# CT.net
KiCad netlist of a schematic drawn in EasyEDA Pro
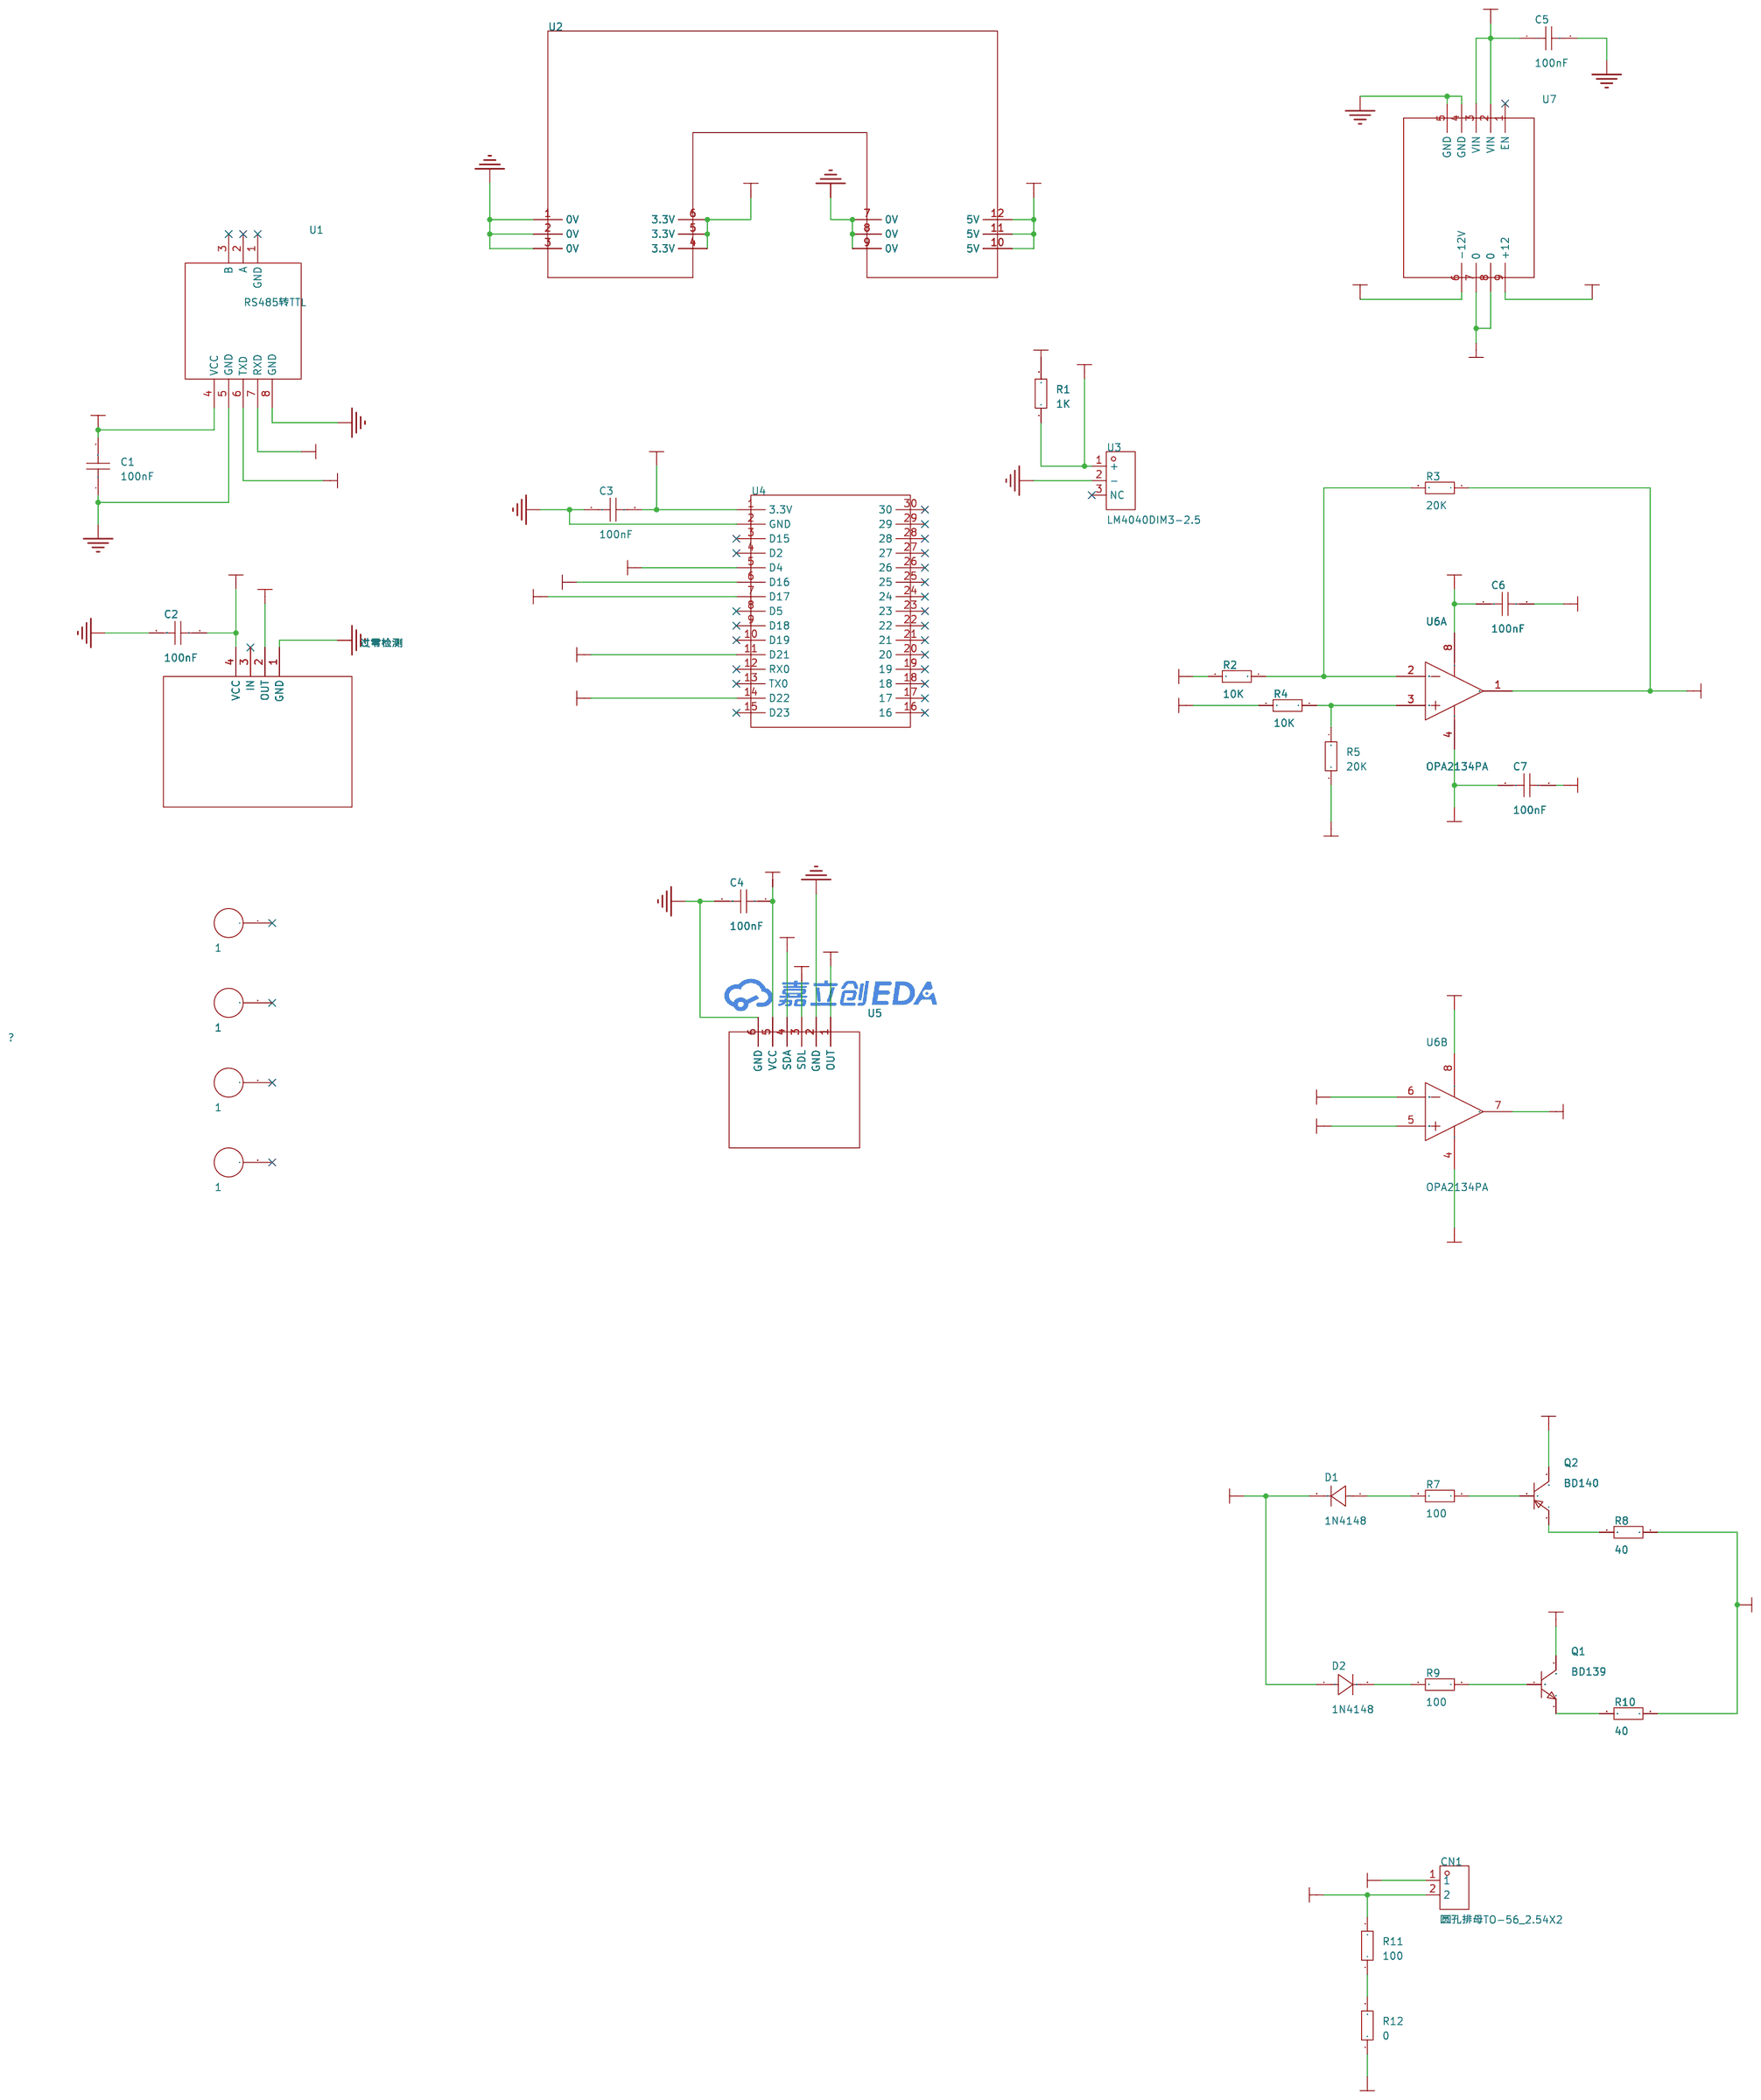
[diagram p0: schematic sheet]

(export (version "E")
  (design (tool "Eeschema 10.0.6"))
  (components
    (comp (ref "C1")
      (value "100nF")
      (footprint "easyedapro:C0805")
      (description "容值:100uF;精度:±20%;额定电压:4V;温度系数:X6S;")
      (fields
        (field (name "Manufacturer Part") "CGA0805X6S107M4R0MT")
        (field (name "Manufacturer") "HRE(芯声)")
      )
      (libsource (lib "easyedapro") (part "CGA0805X6S107M4R0MT"))
    )
    (comp (ref "C2")
      (value "100nF")
      (footprint "easyedapro:C0805")
      (description "容值:100uF;精度:±20%;额定电压:4V;温度系数:X6S;")
      (fields
        (field (name "Manufacturer Part") "CGA0805X6S107M4R0MT")
        (field (name "Manufacturer") "HRE(芯声)")
      )
      (libsource (lib "easyedapro") (part "CGA0805X6S107M4R0MT"))
    )
    (comp (ref "C3")
      (value "100nF")
      (footprint "easyedapro:C0805")
      (description "容值:100uF;精度:±20%;额定电压:4V;温度系数:X6S;")
      (fields
        (field (name "Manufacturer Part") "CGA0805X6S107M4R0MT")
        (field (name "Manufacturer") "HRE(芯声)")
      )
      (libsource (lib "easyedapro") (part "CGA0805X6S107M4R0MT"))
    )
    (comp (ref "C4")
      (value "100nF")
      (footprint "easyedapro:C0805")
      (description "容值:100uF;精度:±20%;额定电压:4V;温度系数:X6S;")
      (fields
        (field (name "Manufacturer Part") "CGA0805X6S107M4R0MT")
        (field (name "Manufacturer") "HRE(芯声)")
      )
      (libsource (lib "easyedapro") (part "CGA0805X6S107M4R0MT"))
    )
    (comp (ref "C5")
      (value "100nF")
      (footprint "easyedapro:C0805")
      (description "容值:100uF;精度:±20%;额定电压:4V;温度系数:X6S;")
      (fields
        (field (name "Manufacturer Part") "CGA0805X6S107M4R0MT")
        (field (name "Manufacturer") "HRE(芯声)")
      )
      (libsource (lib "easyedapro") (part "CGA0805X6S107M4R0MT"))
    )
    (comp (ref "C6")
      (value "100nF")
      (footprint "easyedapro:C0805")
      (description "容值:100uF;精度:±20%;额定电压:4V;温度系数:X6S;")
      (fields
        (field (name "Manufacturer Part") "CGA0805X6S107M4R0MT")
        (field (name "Manufacturer") "HRE(芯声)")
      )
      (libsource (lib "easyedapro") (part "CGA0805X6S107M4R0MT"))
    )
    (comp (ref "C7")
      (value "100nF")
      (footprint "easyedapro:C0805")
      (description "容值:100uF;精度:±20%;额定电压:4V;温度系数:X6S;")
      (fields
        (field (name "Manufacturer Part") "CGA0805X6S107M4R0MT")
        (field (name "Manufacturer") "HRE(芯声)")
      )
      (libsource (lib "easyedapro") (part "CGA0805X6S107M4R0MT"))
    )
    (comp (ref "CN1")
      (value "圆孔排母TO-56_2.54X2")
      (footprint "easyedapro:CONN-TH_TO-56_2.54-2")
      (libsource (lib "easyedapro") (part "圆孔排母TO-56_2.54X2"))
    )
    (comp (ref "D1")
      (value "1N4148")
      (footprint "easyedapro:DO-35_BD2.2-L4.0-D0.50_1N4148")
      (description "正向压降(Vf):1V@10mA;直流反向耐压(Vr):100V;整流电流:150mA;反向恢复时间(Trr):4ns;")
      (fields (field (name "Manufacturer") "LJ(朗捷)"))
      (libsource (lib "easyedapro") (part "1N4148_C18195411"))
    )
    (comp (ref "D2")
      (value "1N4148")
      (footprint "easyedapro:DO-35_BD2.2-L4.0-D0.50_1N4148")
      (description "正向压降(Vf):1V@10mA;直流反向耐压(Vr):100V;整流电流:150mA;反向恢复时间(Trr):4ns;")
      (fields (field (name "Manufacturer") "LJ(朗捷)"))
      (libsource (lib "easyedapro") (part "1N4148_C18195411"))
    )
    (comp (ref "Q1")
      (value "BD139")
      (footprint "easyedapro:TO-126_L7.5-W2.5-P2.3-B")
      (description "晶体管类型:NPN;集电极电流(Ic):1.5A;集射极击穿电压(Vceo):80V;耗散功率(Pd):12.5W;直流电流增益(hFE):63@150mA,2V;")
      (fields (field (name "Manufacturer") "ST(意法半导体)"))
      (libsource (lib "easyedapro") (part "BD139"))
    )
    (comp (ref "Q2")
      (value "BD140")
      (footprint "easyedapro:TO-126_L8.3-W3.5-P2.29-T")
      (description "晶体管类型:PNP;集电极电流(Ic):1.5A;集射极击穿电压(Vceo):80V;耗散功率(Pd):1.25W;直流电流增益(hFE):40@150mA,2V;")
      (fields (field (name "Manufacturer") "CJ(江苏长电/长晶)"))
      (libsource (lib "easyedapro") (part "BD140_C20604"))
    )
    (comp (ref "R1")
      (value "1K")
      (footprint "easyedapro:R0805")
      (description "电阻类型:厚膜电阻;阻值:1MΩ;精度:±1%;功率:125mW;最大工作电压:150V;温度系数:±100ppm/°C;")
      (fields
        (field (name "Manufacturer Part") "0805W8F1004T5E")
        (field (name "Manufacturer") "UNI-ROYAL(厚声)")
      )
      (libsource (lib "easyedapro") (part "0805W8F1004T5E"))
    )
    (comp (ref "R2")
      (value "10K")
      (footprint "easyedapro:R0805")
      (description "电阻类型:厚膜电阻;阻值:1MΩ;精度:±1%;功率:125mW;最大工作电压:150V;温度系数:±100ppm/°C;")
      (fields
        (field (name "Manufacturer Part") "0805W8F1004T5E")
        (field (name "Manufacturer") "UNI-ROYAL(厚声)")
      )
      (libsource (lib "easyedapro") (part "0805W8F1004T5E"))
    )
    (comp (ref "R3")
      (value "20K")
      (footprint "easyedapro:R0805")
      (description "电阻类型:厚膜电阻;阻值:1MΩ;精度:±1%;功率:125mW;最大工作电压:150V;温度系数:±100ppm/°C;")
      (fields
        (field (name "Manufacturer Part") "0805W8F1004T5E")
        (field (name "Manufacturer") "UNI-ROYAL(厚声)")
      )
      (libsource (lib "easyedapro") (part "0805W8F1004T5E"))
    )
    (comp (ref "R4")
      (value "10K")
      (footprint "easyedapro:R0805")
      (description "电阻类型:厚膜电阻;阻值:1MΩ;精度:±1%;功率:125mW;最大工作电压:150V;温度系数:±100ppm/°C;")
      (fields
        (field (name "Manufacturer Part") "0805W8F1004T5E")
        (field (name "Manufacturer") "UNI-ROYAL(厚声)")
      )
      (libsource (lib "easyedapro") (part "0805W8F1004T5E"))
    )
    (comp (ref "R5")
      (value "20K")
      (footprint "easyedapro:R0805")
      (description "电阻类型:厚膜电阻;阻值:1MΩ;精度:±1%;功率:125mW;最大工作电压:150V;温度系数:±100ppm/°C;")
      (fields
        (field (name "Manufacturer Part") "0805W8F1004T5E")
        (field (name "Manufacturer") "UNI-ROYAL(厚声)")
      )
      (libsource (lib "easyedapro") (part "0805W8F1004T5E"))
    )
    (comp (ref "R7")
      (value "100")
      (footprint "easyedapro:R0805")
      (description "电阻类型:厚膜电阻;阻值:1MΩ;精度:±1%;功率:125mW;最大工作电压:150V;温度系数:±100ppm/°C;")
      (fields
        (field (name "Manufacturer Part") "0805W8F1004T5E")
        (field (name "Manufacturer") "UNI-ROYAL(厚声)")
      )
      (libsource (lib "easyedapro") (part "0805W8F1004T5E"))
    )
    (comp (ref "R8")
      (value "40")
      (footprint "easyedapro:R0805")
      (description "电阻类型:厚膜电阻;阻值:1MΩ;精度:±1%;功率:125mW;最大工作电压:150V;温度系数:±100ppm/°C;")
      (fields
        (field (name "Manufacturer Part") "0805W8F1004T5E")
        (field (name "Manufacturer") "UNI-ROYAL(厚声)")
      )
      (libsource (lib "easyedapro") (part "0805W8F1004T5E"))
    )
    (comp (ref "R9")
      (value "100")
      (footprint "easyedapro:R0805")
      (description "电阻类型:厚膜电阻;阻值:1MΩ;精度:±1%;功率:125mW;最大工作电压:150V;温度系数:±100ppm/°C;")
      (fields
        (field (name "Manufacturer Part") "0805W8F1004T5E")
        (field (name "Manufacturer") "UNI-ROYAL(厚声)")
      )
      (libsource (lib "easyedapro") (part "0805W8F1004T5E"))
    )
    (comp (ref "R10")
      (value "40")
      (footprint "easyedapro:R0805")
      (description "电阻类型:厚膜电阻;阻值:1MΩ;精度:±1%;功率:125mW;最大工作电压:150V;温度系数:±100ppm/°C;")
      (fields
        (field (name "Manufacturer Part") "0805W8F1004T5E")
        (field (name "Manufacturer") "UNI-ROYAL(厚声)")
      )
      (libsource (lib "easyedapro") (part "0805W8F1004T5E"))
    )
    (comp (ref "R11")
      (value "100")
      (footprint "easyedapro:R0805")
      (description "电阻类型:厚膜电阻;阻值:1MΩ;精度:±1%;功率:125mW;最大工作电压:150V;温度系数:±100ppm/°C;")
      (fields
        (field (name "Manufacturer Part") "0805W8F1004T5E")
        (field (name "Manufacturer") "UNI-ROYAL(厚声)")
      )
      (libsource (lib "easyedapro") (part "0805W8F1004T5E"))
    )
    (comp (ref "R12")
      (value "0")
      (footprint "easyedapro:R0805")
      (description "电阻类型:厚膜电阻;阻值:1MΩ;精度:±1%;功率:125mW;最大工作电压:150V;温度系数:±100ppm/°C;")
      (fields
        (field (name "Manufacturer Part") "0805W8F1004T5E")
        (field (name "Manufacturer") "UNI-ROYAL(厚声)")
      )
      (libsource (lib "easyedapro") (part "0805W8F1004T5E"))
    )
    (comp (ref "U1")
      (value "RS485转TTL")
      (footprint "easyedapro:RS485转TTL")
      (libsource (lib "easyedapro") (part "元件"))
    )
    (comp (ref "U2")
      (value "~")
      (footprint "easyedapro:9V1A供电")
      (libsource (lib "easyedapro") (part "9V1A供电"))
    )
    (comp (ref "U3")
      (value "LM4040DIM3-2.5")
      (footprint "easyedapro:SOT-23-3_L2.9-W1.3-P1.90-LS2.4-BR")
      (description "输出类型:固定;输出电压:2.5V;输出电流:15mA;精度:±1%;")
      (fields (field (name "Manufacturer") "TI(德州仪器)"))
      (libsource (lib "easyedapro") (part "LM4040DIM3-2.5_C3717666"))
    )
    (comp (ref "U4") (value "~") (footprint "easyedapro:ESP32") (libsource (lib "easyedapro") (part "ESP32")))
    (comp (ref "U5")
      (value "~")
      (footprint "easyedapro:mcp4725")
      (libsource (lib "easyedapro") (part "mcp4725"))
    )
    (comp (ref "U6")
      (value "OPA2134PA")
      (footprint "easyedapro:DIP-8_L9.6-W6.4-P2.54-LS7.6-BL-1")
      (description "功放类型:-;扬声器通道数:双声道;输出功率:-;")
      (fields (field (name "Manufacturer") "TI(德州仪器)"))
      (libsource (lib "easyedapro") (part "OPA2134PA"))
    )
    (comp (ref "U7")
      (value "~")
      (footprint "easyedapro:-12/+12")
      (libsource (lib "easyedapro") (part "-12/+12"))
    )
    (comp (ref "V-PB2")
      (value "1")
      (footprint "easyedapro:SMD_BD4.2-L4.7-W4.7-D3.0")
      (description "M3*5+6")
      (fields (field (name "Manufacturer") "国产"))
      (libsource (lib "easyedapro") (part "铜柱M3*5+6"))
    )
    (comp (ref "V-PB3")
      (value "1")
      (footprint "easyedapro:SMD_BD4.2-L4.7-W4.7-D3.0")
      (description "M3*5+6")
      (fields (field (name "Manufacturer") "国产"))
      (libsource (lib "easyedapro") (part "铜柱M3*5+6"))
    )
    (comp (ref "V-PB4")
      (value "1")
      (footprint "easyedapro:SMD_BD4.2-L4.7-W4.7-D3.0")
      (description "M3*5+6")
      (fields (field (name "Manufacturer") "国产"))
      (libsource (lib "easyedapro") (part "铜柱M3*5+6"))
    )
    (comp (ref "V-PB5")
      (value "1")
      (footprint "easyedapro:SMD_BD4.2-L4.7-W4.7-D3.0")
      (description "M3*5+6")
      (fields (field (name "Manufacturer") "国产"))
      (libsource (lib "easyedapro") (part "铜柱M3*5+6"))
    )
    (comp (ref "过零检测") (value "~") (footprint "easyedapro:过零检测") (libsource (lib "easyedapro") (part "过零检测")))
  )
  (nets
    (net (code "1") (name "+12V") (class "Default")
      (node (ref "C6") (pin "1") (pinfunction "1_1") (pintype "unspecified"))
      (node (ref "Q1") (pin "2") (pinfunction "C_2") (pintype "unspecified"))
      (node (ref "U6") (pin "8") (pinfunction "V+_8") (pintype "unspecified"))
      (node (ref "U7") (pin "9") (pinfunction "+12_9") (pintype "input"))
    )
    (net (code "2") (name "-12V") (class "Default")
      (node (ref "C7") (pin "1") (pinfunction "1_1") (pintype "unspecified"))
      (node (ref "Q2") (pin "2") (pinfunction "C_2") (pintype "input"))
      (node (ref "U6") (pin "4") (pinfunction "V-_4") (pintype "unspecified"))
      (node (ref "U7") (pin "6") (pinfunction "-12V_6") (pintype "input"))
    )
    (net (code "3") (name "0V") (class "Default")
      (node (ref "C6") (pin "2") (pinfunction "2_2") (pintype "unspecified"))
      (node (ref "C7") (pin "2") (pinfunction "2_2") (pintype "unspecified"))
      (node (ref "R12") (pin "1") (pinfunction "1_1") (pintype "input"))
      (node (ref "R5") (pin "2") (pinfunction "2_2") (pintype "input"))
      (node (ref "U7") (pin "7") (pinfunction "0_7") (pintype "input"))
      (node (ref "U7") (pin "8") (pinfunction "0_8") (pintype "input"))
    )
    (net (code "4") (name "3.3V") (class "Default")
      (node (ref "C1") (pin "2") (pinfunction "2_2") (pintype "unspecified"))
      (node (ref "C2") (pin "1") (pinfunction "1_1") (pintype "unspecified"))
      (node (ref "C3") (pin "2") (pinfunction "2_2") (pintype "unspecified"))
      (node (ref "U1") (pin "4") (pinfunction "VCC_4") (pintype "input"))
      (node (ref "U2") (pin "4") (pinfunction "3.3V_4") (pintype "input"))
      (node (ref "U2") (pin "5") (pinfunction "3.3V_5") (pintype "input"))
      (node (ref "U2") (pin "6") (pinfunction "3.3V_6") (pintype "input"))
      (node (ref "U4") (pin "1") (pinfunction "3.3V_1") (pintype "input"))
      (node (ref "过零检测") (pin "4") (pinfunction "VCC_4") (pintype "input"))
    )
    (net (code "5") (name "5V") (class "Default")
      (node (ref "C4") (pin "2") (pinfunction "2_2") (pintype "unspecified"))
      (node (ref "C5") (pin "1") (pinfunction "1_1") (pintype "unspecified"))
      (node (ref "R1") (pin "2") (pinfunction "2_2") (pintype "input"))
      (node (ref "U2") (pin "10") (pinfunction "5V_10") (pintype "input"))
      (node (ref "U2") (pin "11") (pinfunction "5V_11") (pintype "input"))
      (node (ref "U2") (pin "12") (pinfunction "5V_12") (pintype "input"))
      (node (ref "U5") (pin "5") (pinfunction "VCC_5") (pintype "input"))
      (node (ref "U7") (pin "2") (pinfunction "VIN_2") (pintype "input"))
      (node (ref "U7") (pin "3") (pinfunction "VIN_3") (pintype "input"))
    )
    (net (code "6") (name "CT+") (class "Default")
      (node (ref "CN1") (pin "1") (pinfunction "1_1") (pintype "unspecified"))
      (node (ref "R10") (pin "2") (pinfunction "2_2") (pintype "input"))
      (node (ref "R8") (pin "2") (pinfunction "2_2") (pintype "input"))
    )
    (net (code "7") (name "CT-") (class "Default")
      (node (ref "CN1") (pin "2") (pinfunction "2_2") (pintype "unspecified"))
      (node (ref "R11") (pin "2") (pinfunction "2_2") (pintype "input"))
      (node (ref "U6") (pin "6") (pinfunction "-IN_B_6") (pintype "unspecified"))
    )
    (net (code "8") (name "GND") (class "Default")
      (node (ref "C1") (pin "1") (pinfunction "1_1") (pintype "unspecified"))
      (node (ref "C2") (pin "2") (pinfunction "2_2") (pintype "unspecified"))
      (node (ref "C3") (pin "1") (pinfunction "1_1") (pintype "unspecified"))
      (node (ref "C4") (pin "1") (pinfunction "1_1") (pintype "unspecified"))
      (node (ref "C5") (pin "2") (pinfunction "2_2") (pintype "unspecified"))
      (node (ref "U1") (pin "5") (pinfunction "GND_5") (pintype "input"))
      (node (ref "U1") (pin "8") (pinfunction "GND_8") (pintype "input"))
      (node (ref "U2") (pin "1") (pinfunction "0V_1") (pintype "input"))
      (node (ref "U2") (pin "2") (pinfunction "0V_2") (pintype "input"))
      (node (ref "U2") (pin "3") (pinfunction "0V_3") (pintype "input"))
      (node (ref "U2") (pin "7") (pinfunction "0V_7") (pintype "input"))
      (node (ref "U2") (pin "8") (pinfunction "0V_8") (pintype "input"))
      (node (ref "U2") (pin "9") (pinfunction "0V_9") (pintype "input"))
      (node (ref "U3") (pin "2") (pinfunction "-_2") (pintype "unspecified"))
      (node (ref "U4") (pin "2") (pinfunction "GND_2") (pintype "input"))
      (node (ref "U5") (pin "2") (pinfunction "GND_2") (pintype "input"))
      (node (ref "U5") (pin "6") (pinfunction "GND_6") (pintype "input"))
      (node (ref "U7") (pin "4") (pinfunction "GND_4") (pintype "input"))
      (node (ref "U7") (pin "5") (pinfunction "GND_5") (pintype "input"))
      (node (ref "过零检测") (pin "1") (pinfunction "GND_1") (pintype "input"))
    )
    (net (code "9") (name "LM4040_2.5") (class "Default")
      (node (ref "R1") (pin "1") (pinfunction "1_1") (pintype "input"))
      (node (ref "R2") (pin "2") (pinfunction "2_2") (pintype "input"))
      (node (ref "U3") (pin "1") (pinfunction "+_1") (pintype "unspecified"))
    )
    (net (code "10") (name "Net-(D1-A)") (class "Default")
      (node (ref "D1") (pin "1") (pinfunction "A_1") (pintype "unspecified"))
      (node (ref "R7") (pin "2") (pinfunction "2_2") (pintype "input"))
    )
    (net (code "11") (name "Net-(D2-C)") (class "Default")
      (node (ref "D2") (pin "2") (pinfunction "C_2") (pintype "unspecified"))
      (node (ref "R9") (pin "2") (pinfunction "2_2") (pintype "input"))
    )
    (net (code "12") (name "Net-(Q1-B)") (class "Default")
      (node (ref "Q1") (pin "1") (pinfunction "B_1") (pintype "unspecified"))
      (node (ref "R9") (pin "1") (pinfunction "1_1") (pintype "input"))
    )
    (net (code "13") (name "Net-(Q1-E)") (class "Default")
      (node (ref "Q1") (pin "3") (pinfunction "E_3") (pintype "unspecified"))
      (node (ref "R10") (pin "1") (pinfunction "1_1") (pintype "input"))
    )
    (net (code "14") (name "Net-(Q2-B)") (class "Default")
      (node (ref "Q2") (pin "3") (pinfunction "B_3") (pintype "input"))
      (node (ref "R7") (pin "1") (pinfunction "1_1") (pintype "input"))
    )
    (net (code "15") (name "Net-(Q2-E)") (class "Default")
      (node (ref "Q2") (pin "1") (pinfunction "E_1") (pintype "input"))
      (node (ref "R8") (pin "1") (pinfunction "1_1") (pintype "input"))
    )
    (net (code "16") (name "Net-(R11-Pad1)") (class "Default")
      (node (ref "R11") (pin "1") (pinfunction "1_1") (pintype "input"))
      (node (ref "R12") (pin "2") (pinfunction "2_2") (pintype "input"))
    )
    (net (code "17") (name "Net-(U6A-+IN_A)") (class "Default")
      (node (ref "R4") (pin "1") (pinfunction "1_1") (pintype "input"))
      (node (ref "R5") (pin "1") (pinfunction "1_1") (pintype "input"))
      (node (ref "U6") (pin "3") (pinfunction "+IN_A_3") (pintype "unspecified"))
    )
    (net (code "18") (name "Net-(U6A--IN_A)") (class "Default")
      (node (ref "R2") (pin "1") (pinfunction "1_1") (pintype "input"))
      (node (ref "R3") (pin "2") (pinfunction "2_2") (pintype "input"))
      (node (ref "U6") (pin "2") (pinfunction "-IN_A_2") (pintype "unspecified"))
    )
    (net (code "19") (name "OUT_0") (class "Default")
      (node (ref "U4") (pin "5") (pinfunction "D4_5") (pintype "input"))
      (node (ref "过零检测") (pin "2") (pinfunction "OUT_2") (pintype "input"))
    )
    (net (code "20") (name "OUT_MCP4725") (class "Default")
      (node (ref "R4") (pin "2") (pinfunction "2_2") (pintype "input"))
      (node (ref "U5") (pin "1") (pinfunction "OUT_1") (pintype "input"))
    )
    (net (code "21") (name "RX") (class "Default")
      (node (ref "U1") (pin "7") (pinfunction "RXD_7") (pintype "input"))
      (node (ref "U4") (pin "6") (pinfunction "D16_6") (pintype "input"))
    )
    (net (code "22") (name "SDA") (class "Default")
      (node (ref "U4") (pin "11") (pinfunction "D21_11") (pintype "input"))
      (node (ref "U5") (pin "4") (pinfunction "SDA_4") (pintype "input"))
    )
    (net (code "23") (name "SDL") (class "Default")
      (node (ref "U4") (pin "14") (pinfunction "D22_14") (pintype "input"))
      (node (ref "U5") (pin "3") (pinfunction "SDL_3") (pintype "input"))
    )
    (net (code "24") (name "TX") (class "Default")
      (node (ref "U1") (pin "6") (pinfunction "TXD_6") (pintype "input"))
      (node (ref "U4") (pin "7") (pinfunction "D17_7") (pintype "input"))
    )
    (net (code "25") (name "VOUT1") (class "Default")
      (node (ref "R3") (pin "1") (pinfunction "1_1") (pintype "input"))
      (node (ref "U6") (pin "1") (pinfunction "OUT_A_1") (pintype "output"))
      (node (ref "U6") (pin "5") (pinfunction "+IN_B_5") (pintype "unspecified"))
    )
    (net (code "26") (name "VOUT2") (class "Default")
      (node (ref "D1") (pin "2") (pinfunction "C_2") (pintype "unspecified"))
      (node (ref "D2") (pin "1") (pinfunction "A_1") (pintype "unspecified"))
      (node (ref "U6") (pin "7") (pinfunction "OUT_B_7") (pintype "output"))
    )
    (net (code "27") (name "unconnected-(U1-A-Pad2)") (class "Default")
      (node (ref "U1") (pin "2") (pinfunction "A_2") (pintype "input+no_connect"))
    )
    (net (code "28") (name "unconnected-(U1-B-Pad3)") (class "Default")
      (node (ref "U1") (pin "3") (pinfunction "B_3") (pintype "input+no_connect"))
    )
    (net (code "29") (name "unconnected-(U1-GND-Pad1)") (class "Default")
      (node (ref "U1") (pin "1") (pinfunction "GND_1") (pintype "input+no_connect"))
    )
    (net (code "30") (name "unconnected-(U3-NC-Pad3)") (class "Default")
      (node (ref "U3") (pin "3") (pinfunction "NC_3") (pintype "unspecified+no_connect"))
    )
    (net (code "31") (name "unconnected-(U4-D2-Pad4)") (class "Default")
      (node (ref "U4") (pin "4") (pinfunction "D2_4") (pintype "input+no_connect"))
    )
    (net (code "32") (name "unconnected-(U4-D5-Pad8)") (class "Default")
      (node (ref "U4") (pin "8") (pinfunction "D5_8") (pintype "input+no_connect"))
    )
    (net (code "33") (name "unconnected-(U4-D15-Pad3)") (class "Default")
      (node (ref "U4") (pin "3") (pinfunction "D15_3") (pintype "input+no_connect"))
    )
    (net (code "34") (name "unconnected-(U4-D18-Pad9)") (class "Default")
      (node (ref "U4") (pin "9") (pinfunction "D18_9") (pintype "input+no_connect"))
    )
    (net (code "35") (name "unconnected-(U4-D19-Pad10)") (class "Default")
      (node (ref "U4") (pin "10") (pinfunction "D19_10") (pintype "input+no_connect"))
    )
    (net (code "36") (name "unconnected-(U4-D23-Pad15)") (class "Default")
      (node (ref "U4") (pin "15") (pinfunction "D23_15") (pintype "input+no_connect"))
    )
    (net (code "37") (name "unconnected-(U4-Pad16)") (class "Default")
      (node (ref "U4") (pin "16") (pinfunction "16_16") (pintype "input+no_connect"))
    )
    (net (code "38") (name "unconnected-(U4-Pad17)") (class "Default")
      (node (ref "U4") (pin "17") (pinfunction "17_17") (pintype "input+no_connect"))
    )
    (net (code "39") (name "unconnected-(U4-Pad18)") (class "Default")
      (node (ref "U4") (pin "18") (pinfunction "18_18") (pintype "input+no_connect"))
    )
    (net (code "40") (name "unconnected-(U4-Pad19)") (class "Default")
      (node (ref "U4") (pin "19") (pinfunction "19_19") (pintype "input+no_connect"))
    )
    (net (code "41") (name "unconnected-(U4-Pad20)") (class "Default")
      (node (ref "U4") (pin "20") (pinfunction "20_20") (pintype "input+no_connect"))
    )
    (net (code "42") (name "unconnected-(U4-Pad21)") (class "Default")
      (node (ref "U4") (pin "21") (pinfunction "21_21") (pintype "input+no_connect"))
    )
    (net (code "43") (name "unconnected-(U4-Pad22)") (class "Default")
      (node (ref "U4") (pin "22") (pinfunction "22_22") (pintype "input+no_connect"))
    )
    (net (code "44") (name "unconnected-(U4-Pad23)") (class "Default")
      (node (ref "U4") (pin "23") (pinfunction "23_23") (pintype "input+no_connect"))
    )
    (net (code "45") (name "unconnected-(U4-Pad24)") (class "Default")
      (node (ref "U4") (pin "24") (pinfunction "24_24") (pintype "input+no_connect"))
    )
    (net (code "46") (name "unconnected-(U4-Pad25)") (class "Default")
      (node (ref "U4") (pin "25") (pinfunction "25_25") (pintype "input+no_connect"))
    )
    (net (code "47") (name "unconnected-(U4-Pad26)") (class "Default")
      (node (ref "U4") (pin "26") (pinfunction "26_26") (pintype "input+no_connect"))
    )
    (net (code "48") (name "unconnected-(U4-Pad27)") (class "Default")
      (node (ref "U4") (pin "27") (pinfunction "27_27") (pintype "input+no_connect"))
    )
    (net (code "49") (name "unconnected-(U4-Pad28)") (class "Default")
      (node (ref "U4") (pin "28") (pinfunction "28_28") (pintype "input+no_connect"))
    )
    (net (code "50") (name "unconnected-(U4-Pad29)") (class "Default")
      (node (ref "U4") (pin "29") (pinfunction "29_29") (pintype "input+no_connect"))
    )
    (net (code "51") (name "unconnected-(U4-Pad30)") (class "Default")
      (node (ref "U4") (pin "30") (pinfunction "30_30") (pintype "input+no_connect"))
    )
    (net (code "52") (name "unconnected-(U4-RX0-Pad12)") (class "Default")
      (node (ref "U4") (pin "12") (pinfunction "RX0_12") (pintype "input+no_connect"))
    )
    (net (code "53") (name "unconnected-(U4-TX0-Pad13)") (class "Default")
      (node (ref "U4") (pin "13") (pinfunction "TX0_13") (pintype "input+no_connect"))
    )
    (net (code "54") (name "unconnected-(U7-EN-Pad1)") (class "Default")
      (node (ref "U7") (pin "1") (pinfunction "EN_1") (pintype "input+no_connect"))
    )
    (net (code "55") (name "unconnected-(V-PB2-Pad1)") (class "Default")
      (node (ref "V-PB2") (pin "1") (pinfunction "1_1") (pintype "unspecified+no_connect"))
    )
    (net (code "56") (name "unconnected-(V-PB3-Pad1)") (class "Default")
      (node (ref "V-PB3") (pin "1") (pinfunction "1_1") (pintype "unspecified+no_connect"))
    )
    (net (code "57") (name "unconnected-(V-PB4-Pad1)") (class "Default")
      (node (ref "V-PB4") (pin "1") (pinfunction "1_1") (pintype "unspecified+no_connect"))
    )
    (net (code "58") (name "unconnected-(V-PB5-Pad1)") (class "Default")
      (node (ref "V-PB5") (pin "1") (pinfunction "1_1") (pintype "unspecified+no_connect"))
    )
    (net (code "59") (name "unconnected-(过零检测-IN-Pad3)") (class "Default")
      (node (ref "过零检测") (pin "3") (pinfunction "IN_3") (pintype "input+no_connect"))
    )
  )
)
